# M111.net
KiCad netlist of a schematic drawn in EAGLE
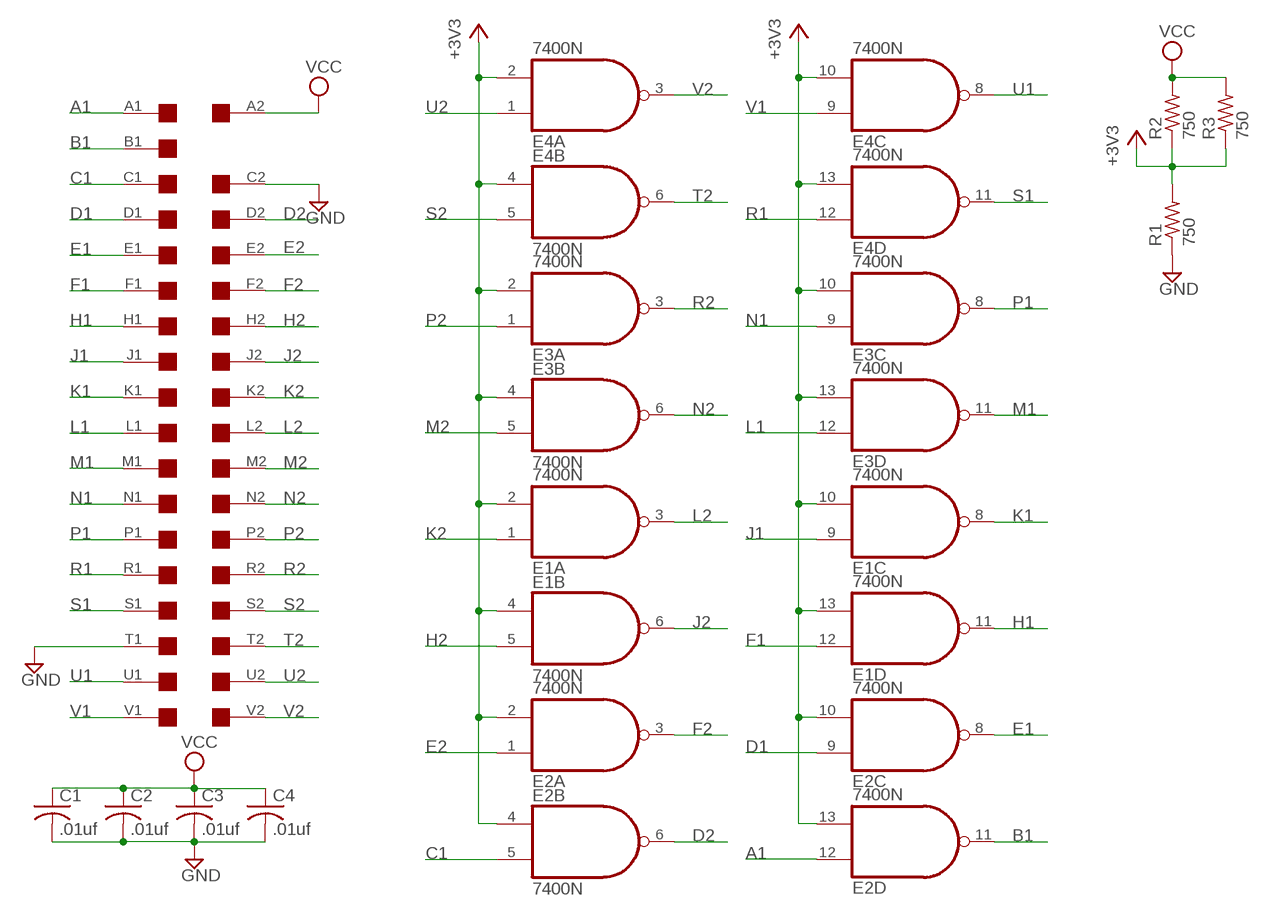
[diagram p0: schematic, sheet 1]

(export (version "E")
  (design (tool "Eeschema 10.0.6"))
  (components
    (comp (ref "A")
      (value "EDGE-2CONNECTOR")
      (footprint "eagle-import:EDGE-CON2")
      (libsource (lib "eagle-import") (part "EDGE-2CONNECTOR"))
    )
    (comp (ref "C1")
      (value ".01uf")
      (footprint "eagle-import:C050-025X075")
      (libsource (lib "eagle-import") (part "C-US050-025X075"))
    )
    (comp (ref "C2")
      (value ".01uf")
      (footprint "eagle-import:C050-025X075")
      (libsource (lib "eagle-import") (part "C-US050-025X075"))
    )
    (comp (ref "C3")
      (value ".01uf")
      (footprint "eagle-import:C050-025X075")
      (libsource (lib "eagle-import") (part "C-US050-025X075"))
    )
    (comp (ref "C4")
      (value ".01uf")
      (footprint "eagle-import:C050-025X075")
      (libsource (lib "eagle-import") (part "C-US050-025X075"))
    )
    (comp (ref "E1")
      (value "7400N")
      (footprint "eagle-import:DIL14")
      (libsource (lib "eagle-import") (part "7400N"))
    )
    (comp (ref "E2")
      (value "7400N")
      (footprint "eagle-import:DIL14")
      (libsource (lib "eagle-import") (part "7400N"))
    )
    (comp (ref "E3")
      (value "7400N")
      (footprint "eagle-import:DIL14")
      (libsource (lib "eagle-import") (part "7400N"))
    )
    (comp (ref "E4")
      (value "7400N")
      (footprint "eagle-import:DIL14")
      (libsource (lib "eagle-import") (part "7400N"))
    )
    (comp (ref "R1")
      (value "750")
      (footprint "eagle-import:0207_10")
      (libsource (lib "eagle-import") (part "R-US_0207/10"))
    )
    (comp (ref "R2")
      (value "750")
      (footprint "eagle-import:0207_10")
      (libsource (lib "eagle-import") (part "R-US_0207/10"))
    )
    (comp (ref "R3")
      (value "750")
      (footprint "eagle-import:0207_10")
      (libsource (lib "eagle-import") (part "R-US_0207/10"))
    )
  )
  (nets
    (net (code "1") (name "+3V3") (class "Default")
      (node (ref "E1") (pin "10") (pinfunction "I1_10") (pintype "input"))
      (node (ref "E1") (pin "13") (pinfunction "I1_13") (pintype "input"))
      (node (ref "E1") (pin "2") (pinfunction "I1_2") (pintype "input"))
      (node (ref "E1") (pin "4") (pinfunction "I0_4") (pintype "input"))
      (node (ref "E2") (pin "10") (pinfunction "I1_10") (pintype "input"))
      (node (ref "E2") (pin "13") (pinfunction "I1_13") (pintype "input"))
      (node (ref "E2") (pin "2") (pinfunction "I1_2") (pintype "input"))
      (node (ref "E2") (pin "4") (pinfunction "I0_4") (pintype "input"))
      (node (ref "E3") (pin "10") (pinfunction "I1_10") (pintype "input"))
      (node (ref "E3") (pin "13") (pinfunction "I1_13") (pintype "input"))
      (node (ref "E3") (pin "2") (pinfunction "I1_2") (pintype "input"))
      (node (ref "E3") (pin "4") (pinfunction "I0_4") (pintype "input"))
      (node (ref "E4") (pin "10") (pinfunction "I1_10") (pintype "input"))
      (node (ref "E4") (pin "13") (pinfunction "I1_13") (pintype "input"))
      (node (ref "E4") (pin "2") (pinfunction "I1_2") (pintype "input"))
      (node (ref "E4") (pin "4") (pinfunction "I0_4") (pintype "input"))
      (node (ref "R1") (pin "2") (pinfunction "2_2") (pintype "passive"))
      (node (ref "R2") (pin "1") (pinfunction "1_1") (pintype "passive"))
      (node (ref "R3") (pin "1") (pinfunction "1_1") (pintype "passive"))
    )
    (net (code "2") (name "/A1") (class "Default")
      (node (ref "A") (pin "A1") (pinfunction "1_A1") (pintype "bidirectional"))
      (node (ref "E2") (pin "12") (pinfunction "I0_12") (pintype "input"))
    )
    (net (code "3") (name "/B1") (class "Default")
      (node (ref "A") (pin "B1") (pinfunction "1_B1") (pintype "bidirectional"))
      (node (ref "E2") (pin "11") (pinfunction "O_11") (pintype "output"))
    )
    (net (code "4") (name "/C1") (class "Default")
      (node (ref "A") (pin "C1") (pinfunction "1_C1") (pintype "bidirectional"))
      (node (ref "E2") (pin "5") (pinfunction "I1_5") (pintype "input"))
    )
    (net (code "5") (name "/D1") (class "Default")
      (node (ref "A") (pin "D1") (pinfunction "1_D1") (pintype "bidirectional"))
      (node (ref "E2") (pin "9") (pinfunction "I0_9") (pintype "input"))
    )
    (net (code "6") (name "/D2") (class "Default")
      (node (ref "A") (pin "D2") (pinfunction "1_D2") (pintype "bidirectional"))
      (node (ref "E2") (pin "6") (pinfunction "O_6") (pintype "output"))
    )
    (net (code "7") (name "/E1") (class "Default")
      (node (ref "A") (pin "E1") (pinfunction "1_E1") (pintype "bidirectional"))
      (node (ref "E2") (pin "8") (pinfunction "O_8") (pintype "output"))
    )
    (net (code "8") (name "/E2") (class "Default")
      (node (ref "A") (pin "E2") (pinfunction "1_E2") (pintype "bidirectional"))
      (node (ref "E2") (pin "1") (pinfunction "I0_1") (pintype "input"))
    )
    (net (code "9") (name "/F1") (class "Default")
      (node (ref "A") (pin "F1") (pinfunction "1_F1") (pintype "bidirectional"))
      (node (ref "E1") (pin "12") (pinfunction "I0_12") (pintype "input"))
    )
    (net (code "10") (name "/F2") (class "Default")
      (node (ref "A") (pin "F2") (pinfunction "1_F2") (pintype "bidirectional"))
      (node (ref "E2") (pin "3") (pinfunction "O_3") (pintype "output"))
    )
    (net (code "11") (name "/H1") (class "Default")
      (node (ref "A") (pin "H1") (pinfunction "1_H1") (pintype "bidirectional"))
      (node (ref "E1") (pin "11") (pinfunction "O_11") (pintype "output"))
    )
    (net (code "12") (name "/H2") (class "Default")
      (node (ref "A") (pin "H2") (pinfunction "1_H2") (pintype "bidirectional"))
      (node (ref "E1") (pin "5") (pinfunction "I1_5") (pintype "input"))
    )
    (net (code "13") (name "/J1") (class "Default")
      (node (ref "A") (pin "J1") (pinfunction "1_J1") (pintype "bidirectional"))
      (node (ref "E1") (pin "9") (pinfunction "I0_9") (pintype "input"))
    )
    (net (code "14") (name "/J2") (class "Default")
      (node (ref "A") (pin "J2") (pinfunction "1_J2") (pintype "bidirectional"))
      (node (ref "E1") (pin "6") (pinfunction "O_6") (pintype "output"))
    )
    (net (code "15") (name "/K1") (class "Default")
      (node (ref "A") (pin "K1") (pinfunction "1_K1") (pintype "bidirectional"))
      (node (ref "E1") (pin "8") (pinfunction "O_8") (pintype "output"))
    )
    (net (code "16") (name "/K2") (class "Default")
      (node (ref "A") (pin "K2") (pinfunction "1_K2") (pintype "bidirectional"))
      (node (ref "E1") (pin "1") (pinfunction "I0_1") (pintype "input"))
    )
    (net (code "17") (name "/L1") (class "Default")
      (node (ref "A") (pin "L1") (pinfunction "1_L1") (pintype "bidirectional"))
      (node (ref "E3") (pin "12") (pinfunction "I0_12") (pintype "input"))
    )
    (net (code "18") (name "/L2") (class "Default")
      (node (ref "A") (pin "L2") (pinfunction "1_L2") (pintype "bidirectional"))
      (node (ref "E1") (pin "3") (pinfunction "O_3") (pintype "output"))
    )
    (net (code "19") (name "/M1") (class "Default")
      (node (ref "A") (pin "M1") (pinfunction "1_M1") (pintype "bidirectional"))
      (node (ref "E3") (pin "11") (pinfunction "O_11") (pintype "output"))
    )
    (net (code "20") (name "/M2") (class "Default")
      (node (ref "A") (pin "M2") (pinfunction "1_M2") (pintype "bidirectional"))
      (node (ref "E3") (pin "5") (pinfunction "I1_5") (pintype "input"))
    )
    (net (code "21") (name "/N1") (class "Default")
      (node (ref "A") (pin "N1") (pinfunction "1_N1") (pintype "bidirectional"))
      (node (ref "E3") (pin "9") (pinfunction "I0_9") (pintype "input"))
    )
    (net (code "22") (name "/N2") (class "Default")
      (node (ref "A") (pin "N2") (pinfunction "1_N2") (pintype "bidirectional"))
      (node (ref "E3") (pin "6") (pinfunction "O_6") (pintype "output"))
    )
    (net (code "23") (name "/P1") (class "Default")
      (node (ref "A") (pin "P1") (pinfunction "1_P1") (pintype "bidirectional"))
      (node (ref "E3") (pin "8") (pinfunction "O_8") (pintype "output"))
    )
    (net (code "24") (name "/P2") (class "Default")
      (node (ref "A") (pin "P2") (pinfunction "1_P2") (pintype "bidirectional"))
      (node (ref "E3") (pin "1") (pinfunction "I0_1") (pintype "input"))
    )
    (net (code "25") (name "/R1") (class "Default")
      (node (ref "A") (pin "R1") (pinfunction "1_R1") (pintype "bidirectional"))
      (node (ref "E4") (pin "12") (pinfunction "I0_12") (pintype "input"))
    )
    (net (code "26") (name "/R2") (class "Default")
      (node (ref "A") (pin "R2") (pinfunction "1_R2") (pintype "bidirectional"))
      (node (ref "E3") (pin "3") (pinfunction "O_3") (pintype "output"))
    )
    (net (code "27") (name "/S1") (class "Default")
      (node (ref "A") (pin "S1") (pinfunction "1_S1") (pintype "bidirectional"))
      (node (ref "E4") (pin "11") (pinfunction "O_11") (pintype "output"))
    )
    (net (code "28") (name "/S2") (class "Default")
      (node (ref "A") (pin "S2") (pinfunction "1_S2") (pintype "bidirectional"))
      (node (ref "E4") (pin "5") (pinfunction "I1_5") (pintype "input"))
    )
    (net (code "29") (name "/T2") (class "Default")
      (node (ref "A") (pin "T2") (pinfunction "1_T2") (pintype "bidirectional"))
      (node (ref "E4") (pin "6") (pinfunction "O_6") (pintype "output"))
    )
    (net (code "30") (name "/U1") (class "Default")
      (node (ref "A") (pin "U1") (pinfunction "1_U1") (pintype "bidirectional"))
      (node (ref "E4") (pin "8") (pinfunction "O_8") (pintype "output"))
    )
    (net (code "31") (name "/U2") (class "Default")
      (node (ref "A") (pin "U2") (pinfunction "1_U2") (pintype "bidirectional"))
      (node (ref "E4") (pin "1") (pinfunction "I0_1") (pintype "input"))
    )
    (net (code "32") (name "/V1") (class "Default")
      (node (ref "A") (pin "V1") (pinfunction "1_V1") (pintype "bidirectional"))
      (node (ref "E4") (pin "9") (pinfunction "I0_9") (pintype "input"))
    )
    (net (code "33") (name "/V2") (class "Default")
      (node (ref "A") (pin "V2") (pinfunction "1_V2") (pintype "bidirectional"))
      (node (ref "E4") (pin "3") (pinfunction "O_3") (pintype "output"))
    )
    (net (code "34") (name "GND") (class "Default")
      (node (ref "A") (pin "C2") (pinfunction "1_C2") (pintype "bidirectional"))
      (node (ref "A") (pin "T1") (pinfunction "1_T1") (pintype "bidirectional"))
      (node (ref "C1") (pin "2") (pinfunction "2_2") (pintype "passive"))
      (node (ref "C2") (pin "2") (pinfunction "2_2") (pintype "passive"))
      (node (ref "C3") (pin "2") (pinfunction "2_2") (pintype "passive"))
      (node (ref "C4") (pin "2") (pinfunction "2_2") (pintype "passive"))
      (node (ref "R1") (pin "1") (pinfunction "1_1") (pintype "passive"))
    )
    (net (code "35") (name "VCC") (class "Default")
      (node (ref "A") (pin "A2") (pinfunction "1_A2") (pintype "bidirectional"))
      (node (ref "C1") (pin "1") (pinfunction "1_1") (pintype "passive"))
      (node (ref "C2") (pin "1") (pinfunction "1_1") (pintype "passive"))
      (node (ref "C3") (pin "1") (pinfunction "1_1") (pintype "passive"))
      (node (ref "C4") (pin "1") (pinfunction "1_1") (pintype "passive"))
      (node (ref "R2") (pin "2") (pinfunction "2_2") (pintype "passive"))
      (node (ref "R3") (pin "2") (pinfunction "2_2") (pintype "passive"))
    )
  )
)
